# MCU.net
KiCad netlist of a schematic drawn in Altium Designer
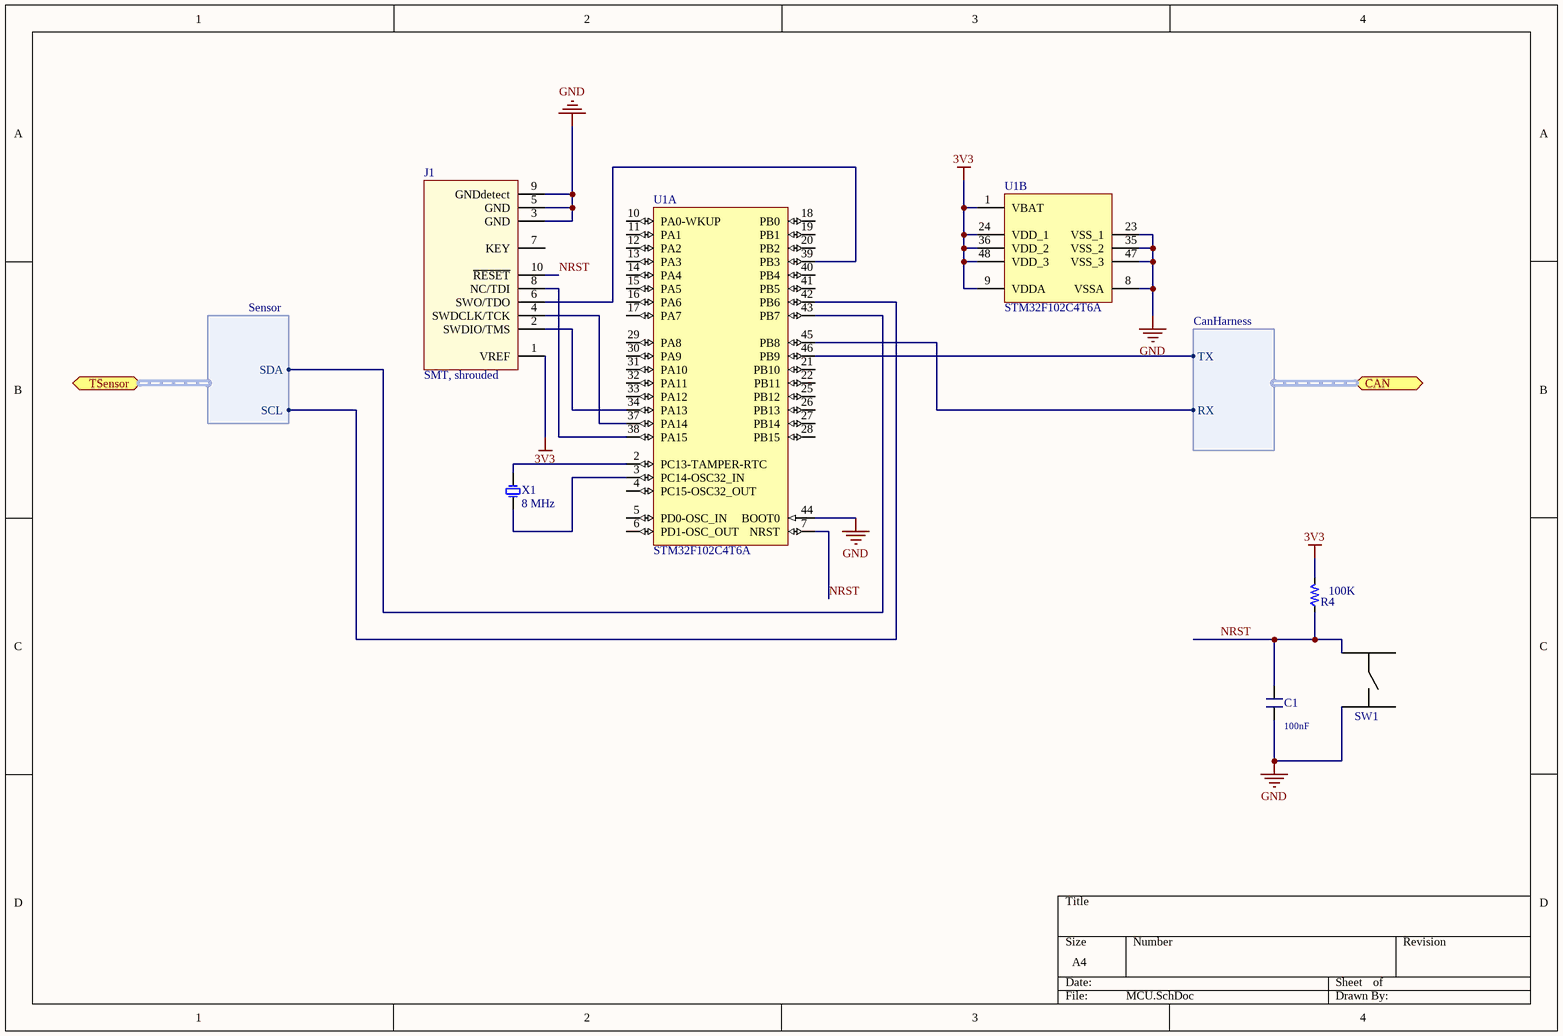
[diagram p0: MCU.SchDoc]

(export (version "E")
  (design (tool "Eeschema 10.0.6"))
  (components
    (comp (ref "C1")
      (value "SCH_GENERIC_CAPACITOR_0603")
      (footprint "PCB_GENERIC_SMD_0603")
      (description "Generic SMD capacitor 0603")
      (fields (field (name "TOLERANCE") "*%") (field (name "CAPACITANCE") "100nF"))
      (libsource (lib "Generic 0603 Capacitor") (part "SCH_GENERIC_CAPACITOR_0603"))
    )
    (comp (ref "J1")
      (value "SMT, shrouded")
      (footprint "CONN-50mil-10POS-SMD")
      (description "ARM Cortex-M 10pin connector,shrouded,SMT")
      (libsource (lib "CONN-50mil-cortexM") (part "conn_0.050{dblquote}_cortexM"))
    )
    (comp (ref "R4")
      (value "SCH_GENERIC_RESISTOR_0603")
      (footprint "PCB_GENERIC_SMD_0603")
      (description "Generic SMD resistor 0603")
      (fields (field (name "RESISTANCE") "100K"))
      (libsource (lib "Generic 0603 Resistor") (part "SCH_GENERIC_RESISTOR_0603"))
    )
    (comp (ref "SW1")
      (value "Tactile Switch")
      (footprint "C&K 4 pin Tactile Switch")
      (libsource (lib "C&K 4 Pin Tactile Switch") (part "C&K Tactile Switch"))
    )
    (comp (ref "U1")
      (value "STM32F102C4T6A")
      (footprint "STM-LQFP48_N")
      (libsource (lib "STMicroelectronics STM32 F1") (part "STM32F102C4T6A"))
    )
    (comp (ref "X1")
      (value "8 MHz")
      (footprint "CRYSTAL_8MHZ")
      (description "8MHz ±30ppm 20pF Crystal")
      (libsource (lib "Foxslf 8MHz Crystal") (part "XTAL_TH_8MHz"))
    )
  )
  (nets
    (net (code "3") (name "/NRST") (class "Default")
      (node (ref "C1") (pin "2") (pinfunction "2_2") (pintype "passive"))
      (node (ref "J1") (pin "10") (pinfunction "~{RESET}_10") (pintype "passive"))
      (node (ref "R4") (pin "1") (pinfunction "1_1") (pintype "passive"))
      (node (ref "SW1") (pin "1") (pintype "passive"))
      (node (ref "U1") (pin "7") (pinfunction "NRST_7") (pintype "bidirectional"))
    )
    (net (code "4") (name "/RX") (class "Default")
      (node (ref "U1") (pin "45") (pinfunction "PB8_45") (pintype "bidirectional"))
    )
    (net (code "5") (name "/SCL") (class "Default")
      (node (ref "U1") (pin "42") (pinfunction "PB6_42") (pintype "bidirectional"))
    )
    (net (code "6") (name "/SDA") (class "Default")
      (node (ref "U1") (pin "43") (pinfunction "PB7_43") (pintype "bidirectional"))
    )
    (net (code "7") (name "/TX") (class "Default")
      (node (ref "U1") (pin "46") (pinfunction "PB9_46") (pintype "bidirectional"))
    )
    (net (code "10") (name "3V3") (class "Default")
      (node (ref "J1") (pin "1") (pinfunction "VREF_1") (pintype "passive"))
      (node (ref "R4") (pin "2") (pinfunction "2_2") (pintype "passive"))
      (node (ref "U1") (pin "1") (pinfunction "VBAT_1") (pintype "power_in"))
      (node (ref "U1") (pin "24") (pinfunction "VDD_1_24") (pintype "power_in"))
      (node (ref "U1") (pin "36") (pinfunction "VDD_2_36") (pintype "power_in"))
      (node (ref "U1") (pin "48") (pinfunction "VDD_3_48") (pintype "power_in"))
      (node (ref "U1") (pin "9") (pinfunction "VDDA_9") (pintype "power_in"))
    )
    (net (code "11") (name "GND") (class "Default")
      (node (ref "C1") (pin "1") (pinfunction "1_1") (pintype "passive"))
      (node (ref "J1") (pin "3") (pinfunction "GND_3") (pintype "passive"))
      (node (ref "J1") (pin "5") (pinfunction "GND_5") (pintype "passive"))
      (node (ref "J1") (pin "9") (pinfunction "GNDdetect_9") (pintype "passive"))
      (node (ref "SW1") (pin "3") (pinfunction "3_3") (pintype "passive"))
      (node (ref "U1") (pin "23") (pinfunction "VSS_1_23") (pintype "power_in"))
      (node (ref "U1") (pin "35") (pinfunction "VSS_2_35") (pintype "power_in"))
      (node (ref "U1") (pin "44") (pinfunction "BOOT0_44") (pintype "input"))
      (node (ref "U1") (pin "47") (pinfunction "VSS_3_47") (pintype "power_in"))
      (node (ref "U1") (pin "8") (pinfunction "VSSA_8") (pintype "power_in"))
    )
    (net (code "12") (name "Net-(J1-NC{slash}TDI)") (class "Default")
      (node (ref "J1") (pin "8") (pinfunction "NC/TDI_8") (pintype "passive"))
      (node (ref "U1") (pin "38") (pinfunction "PA15_38") (pintype "bidirectional"))
    )
    (net (code "13") (name "Net-(J1-SWDCLK{slash}TCK)") (class "Default")
      (node (ref "J1") (pin "4") (pinfunction "SWDCLK/TCK_4") (pintype "passive"))
      (node (ref "U1") (pin "37") (pinfunction "PA14_37") (pintype "bidirectional"))
    )
    (net (code "14") (name "Net-(J1-SWDIO{slash}TMS)") (class "Default")
      (node (ref "J1") (pin "2") (pinfunction "SWDIO/TMS_2") (pintype "passive"))
      (node (ref "U1") (pin "34") (pinfunction "PA13_34") (pintype "bidirectional"))
    )
    (net (code "15") (name "Net-(J1-SWO{slash}TDO)") (class "Default")
      (node (ref "J1") (pin "6") (pinfunction "SWO/TDO_6") (pintype "passive"))
      (node (ref "U1") (pin "39") (pinfunction "PB3_39") (pintype "bidirectional"))
    )
    (net (code "16") (name "Net-(U1A-PC13-TAMPER-RTC)") (class "Default")
      (node (ref "U1") (pin "2") (pinfunction "PC13-TAMPER-RTC_2") (pintype "bidirectional"))
      (node (ref "X1") (pin "2") (pintype "passive"))
    )
    (net (code "17") (name "Net-(U1A-PC14-OSC32_IN)") (class "Default")
      (node (ref "U1") (pin "3") (pinfunction "PC14-OSC32_IN_3") (pintype "bidirectional"))
      (node (ref "X1") (pin "1") (pintype "passive"))
    )
    (net (code "18") (name "unconnected-(J1-KEY-Pad7)") (class "Default")
      (node (ref "J1") (pin "7") (pinfunction "KEY_7") (pintype "passive"))
    )
    (net (code "19") (name "unconnected-(SW1-Pad2)") (class "Default")
      (node (ref "SW1") (pin "2") (pinfunction "2_2") (pintype "passive"))
    )
    (net (code "20") (name "unconnected-(SW1-Pad4)") (class "Default")
      (node (ref "SW1") (pin "4") (pinfunction "4_4") (pintype "passive"))
    )
    (net (code "21") (name "unconnected-(U1A-PA0-WKUP-Pad10)") (class "Default")
      (node (ref "U1") (pin "10") (pinfunction "PA0-WKUP_10") (pintype "bidirectional"))
    )
    (net (code "22") (name "unconnected-(U1A-PA1-Pad11)") (class "Default")
      (node (ref "U1") (pin "11") (pinfunction "PA1_11") (pintype "bidirectional"))
    )
    (net (code "23") (name "unconnected-(U1A-PA2-Pad12)") (class "Default")
      (node (ref "U1") (pin "12") (pinfunction "PA2_12") (pintype "bidirectional"))
    )
    (net (code "24") (name "unconnected-(U1A-PA3-Pad13)") (class "Default")
      (node (ref "U1") (pin "13") (pinfunction "PA3_13") (pintype "bidirectional"))
    )
    (net (code "25") (name "unconnected-(U1A-PA4-Pad14)") (class "Default")
      (node (ref "U1") (pin "14") (pinfunction "PA4_14") (pintype "bidirectional"))
    )
    (net (code "26") (name "unconnected-(U1A-PA5-Pad15)") (class "Default")
      (node (ref "U1") (pin "15") (pinfunction "PA5_15") (pintype "bidirectional"))
    )
    (net (code "27") (name "unconnected-(U1A-PA6-Pad16)") (class "Default")
      (node (ref "U1") (pin "16") (pinfunction "PA6_16") (pintype "bidirectional"))
    )
    (net (code "28") (name "unconnected-(U1A-PA7-Pad17)") (class "Default")
      (node (ref "U1") (pin "17") (pinfunction "PA7_17") (pintype "bidirectional"))
    )
    (net (code "29") (name "unconnected-(U1A-PA8-Pad29)") (class "Default")
      (node (ref "U1") (pin "29") (pinfunction "PA8_29") (pintype "bidirectional"))
    )
    (net (code "30") (name "unconnected-(U1A-PA9-Pad30)") (class "Default")
      (node (ref "U1") (pin "30") (pinfunction "PA9_30") (pintype "bidirectional"))
    )
    (net (code "31") (name "unconnected-(U1A-PA10-Pad31)") (class "Default")
      (node (ref "U1") (pin "31") (pinfunction "PA10_31") (pintype "bidirectional"))
    )
    (net (code "32") (name "unconnected-(U1A-PA11-Pad32)") (class "Default")
      (node (ref "U1") (pin "32") (pinfunction "PA11_32") (pintype "bidirectional"))
    )
    (net (code "33") (name "unconnected-(U1A-PA12-Pad33)") (class "Default")
      (node (ref "U1") (pin "33") (pinfunction "PA12_33") (pintype "bidirectional"))
    )
    (net (code "34") (name "unconnected-(U1A-PB0-Pad18)") (class "Default")
      (node (ref "U1") (pin "18") (pinfunction "PB0_18") (pintype "bidirectional"))
    )
    (net (code "35") (name "unconnected-(U1A-PB1-Pad19)") (class "Default")
      (node (ref "U1") (pin "19") (pinfunction "PB1_19") (pintype "bidirectional"))
    )
    (net (code "36") (name "unconnected-(U1A-PB2-Pad20)") (class "Default")
      (node (ref "U1") (pin "20") (pinfunction "PB2_20") (pintype "bidirectional"))
    )
    (net (code "37") (name "unconnected-(U1A-PB4-Pad40)") (class "Default")
      (node (ref "U1") (pin "40") (pinfunction "PB4_40") (pintype "bidirectional"))
    )
    (net (code "38") (name "unconnected-(U1A-PB5-Pad41)") (class "Default")
      (node (ref "U1") (pin "41") (pinfunction "PB5_41") (pintype "bidirectional"))
    )
    (net (code "39") (name "unconnected-(U1A-PB10-Pad21)") (class "Default")
      (node (ref "U1") (pin "21") (pinfunction "PB10_21") (pintype "bidirectional"))
    )
    (net (code "40") (name "unconnected-(U1A-PB11-Pad22)") (class "Default")
      (node (ref "U1") (pin "22") (pinfunction "PB11_22") (pintype "bidirectional"))
    )
    (net (code "41") (name "unconnected-(U1A-PB12-Pad25)") (class "Default")
      (node (ref "U1") (pin "25") (pinfunction "PB12_25") (pintype "bidirectional"))
    )
    (net (code "42") (name "unconnected-(U1A-PB13-Pad26)") (class "Default")
      (node (ref "U1") (pin "26") (pinfunction "PB13_26") (pintype "bidirectional"))
    )
    (net (code "43") (name "unconnected-(U1A-PB14-Pad27)") (class "Default")
      (node (ref "U1") (pin "27") (pinfunction "PB14_27") (pintype "bidirectional"))
    )
    (net (code "44") (name "unconnected-(U1A-PB15-Pad28)") (class "Default")
      (node (ref "U1") (pin "28") (pinfunction "PB15_28") (pintype "bidirectional"))
    )
    (net (code "45") (name "unconnected-(U1A-PC15-OSC32_OUT-Pad4)") (class "Default")
      (node (ref "U1") (pin "4") (pinfunction "PC15-OSC32_OUT_4") (pintype "bidirectional"))
    )
    (net (code "46") (name "unconnected-(U1A-PD0-OSC_IN-Pad5)") (class "Default")
      (node (ref "U1") (pin "5") (pinfunction "PD0-OSC_IN_5") (pintype "bidirectional"))
    )
    (net (code "47") (name "unconnected-(U1A-PD1-OSC_OUT-Pad6)") (class "Default")
      (node (ref "U1") (pin "6") (pinfunction "PD1-OSC_OUT_6") (pintype "bidirectional"))
    )
  )
)
